# TIA.net
KiCad netlist of a schematic drawn in EAGLE
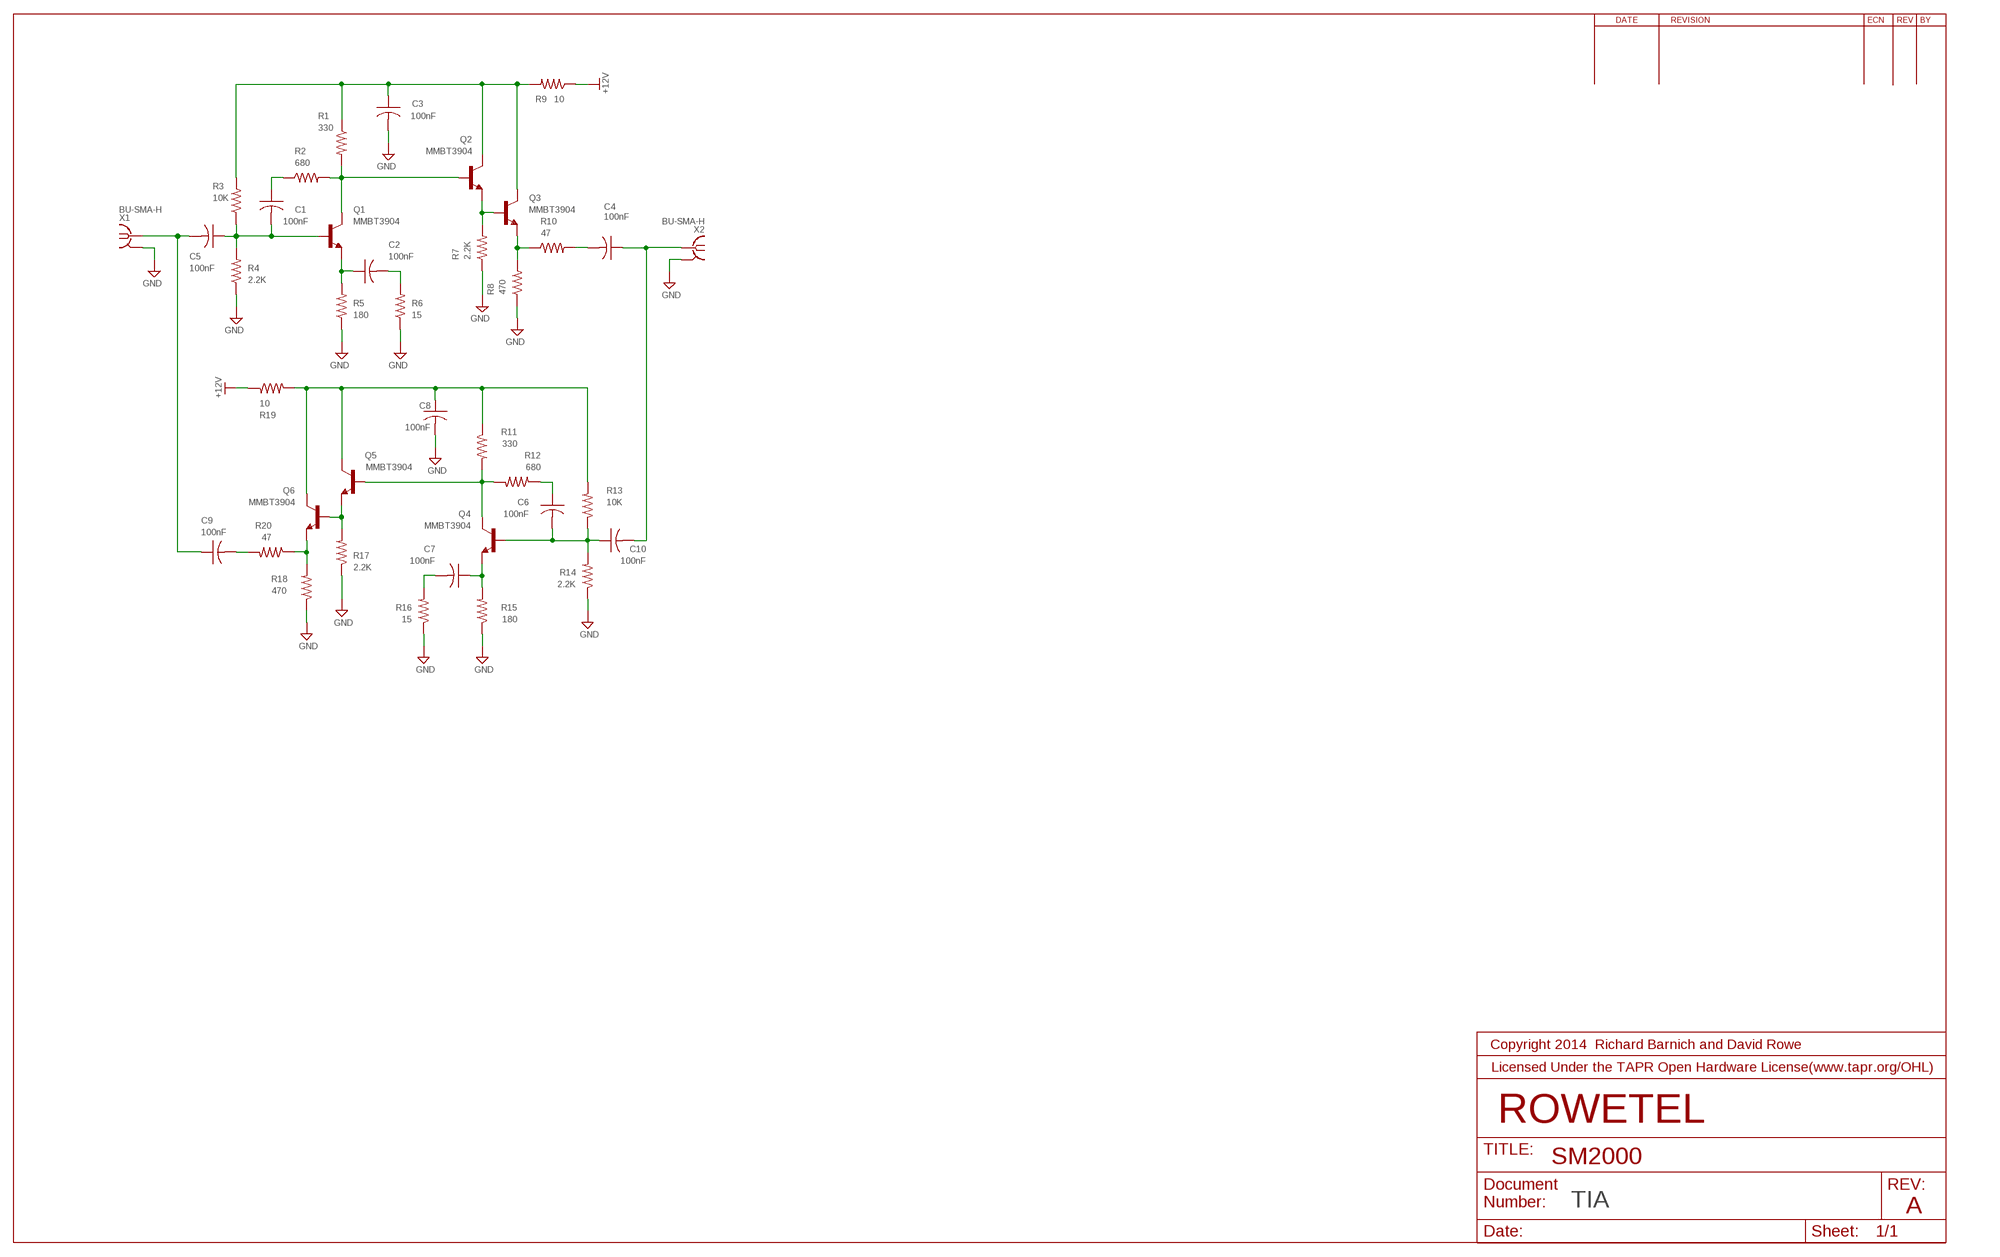
[diagram p0: schematic, sheet 1]

(export (version "E")
  (design (tool "Eeschema 10.0.6"))
  (components
    (comp (ref "C1")
      (value "100nF")
      (footprint "eagle-import:C0805")
      (libsource (lib "eagle-import") (part "CAP-0805"))
    )
    (comp (ref "C2")
      (value "100nF")
      (footprint "eagle-import:C0805")
      (libsource (lib "eagle-import") (part "CAP-0805"))
    )
    (comp (ref "C3")
      (value "100nF")
      (footprint "eagle-import:C0805")
      (libsource (lib "eagle-import") (part "CAP-0805"))
    )
    (comp (ref "C4")
      (value "100nF")
      (footprint "eagle-import:C0805")
      (libsource (lib "eagle-import") (part "CAP-0805"))
    )
    (comp (ref "C5")
      (value "100nF")
      (footprint "eagle-import:C0805")
      (libsource (lib "eagle-import") (part "CAP-0805"))
    )
    (comp (ref "C6")
      (value "100nF")
      (footprint "eagle-import:C0805")
      (libsource (lib "eagle-import") (part "CAP-0805"))
    )
    (comp (ref "C7")
      (value "100nF")
      (footprint "eagle-import:C0805")
      (libsource (lib "eagle-import") (part "CAP-0805"))
    )
    (comp (ref "C8")
      (value "100nF")
      (footprint "eagle-import:C0805")
      (libsource (lib "eagle-import") (part "CAP-0805"))
    )
    (comp (ref "C9")
      (value "100nF")
      (footprint "eagle-import:C0805")
      (libsource (lib "eagle-import") (part "CAP-0805"))
    )
    (comp (ref "C10")
      (value "100nF")
      (footprint "eagle-import:C0805")
      (libsource (lib "eagle-import") (part "CAP-0805"))
    )
    (comp (ref "Q1")
      (value "MMBT3904")
      (footprint "eagle-import:SOT23")
      (libsource (lib "eagle-import") (part "MMBT3904"))
    )
    (comp (ref "Q2")
      (value "MMBT3904")
      (footprint "eagle-import:SOT23")
      (libsource (lib "eagle-import") (part "MMBT3904"))
    )
    (comp (ref "Q3")
      (value "MMBT3904")
      (footprint "eagle-import:SOT23")
      (libsource (lib "eagle-import") (part "MMBT3904"))
    )
    (comp (ref "Q4")
      (value "MMBT3904")
      (footprint "eagle-import:SOT23")
      (libsource (lib "eagle-import") (part "MMBT3904"))
    )
    (comp (ref "Q5")
      (value "MMBT3904")
      (footprint "eagle-import:SOT23")
      (libsource (lib "eagle-import") (part "MMBT3904"))
    )
    (comp (ref "Q6")
      (value "MMBT3904")
      (footprint "eagle-import:SOT23")
      (libsource (lib "eagle-import") (part "MMBT3904"))
    )
    (comp (ref "R1")
      (value "330")
      (footprint "eagle-import:RR0805")
      (libsource (lib "eagle-import") (part "RES0805"))
    )
    (comp (ref "R2")
      (value "680")
      (footprint "eagle-import:RR0805")
      (libsource (lib "eagle-import") (part "RES0805"))
    )
    (comp (ref "R3")
      (value "10K")
      (footprint "eagle-import:RR0805")
      (libsource (lib "eagle-import") (part "RES0805"))
    )
    (comp (ref "R4")
      (value "2.2K")
      (footprint "eagle-import:RR0805")
      (libsource (lib "eagle-import") (part "RES0805"))
    )
    (comp (ref "R5")
      (value "180")
      (footprint "eagle-import:RR0805")
      (libsource (lib "eagle-import") (part "RES0805"))
    )
    (comp (ref "R6")
      (value "15")
      (footprint "eagle-import:RR0805")
      (libsource (lib "eagle-import") (part "RES0805"))
    )
    (comp (ref "R7")
      (value "2.2K")
      (footprint "eagle-import:RR0805")
      (libsource (lib "eagle-import") (part "RES0805"))
    )
    (comp (ref "R8")
      (value "470")
      (footprint "eagle-import:RR0805")
      (libsource (lib "eagle-import") (part "RES0805"))
    )
    (comp (ref "R9")
      (value "10")
      (footprint "eagle-import:RR0805")
      (libsource (lib "eagle-import") (part "RES0805"))
    )
    (comp (ref "R10")
      (value "47")
      (footprint "eagle-import:RR0805")
      (libsource (lib "eagle-import") (part "RES0805"))
    )
    (comp (ref "R11")
      (value "330")
      (footprint "eagle-import:RR0805")
      (libsource (lib "eagle-import") (part "RES0805"))
    )
    (comp (ref "R12")
      (value "680")
      (footprint "eagle-import:RR0805")
      (libsource (lib "eagle-import") (part "RES0805"))
    )
    (comp (ref "R13")
      (value "10K")
      (footprint "eagle-import:RR0805")
      (libsource (lib "eagle-import") (part "RES0805"))
    )
    (comp (ref "R14")
      (value "2.2K")
      (footprint "eagle-import:RR0805")
      (libsource (lib "eagle-import") (part "RES0805"))
    )
    (comp (ref "R15")
      (value "180")
      (footprint "eagle-import:RR0805")
      (libsource (lib "eagle-import") (part "RES0805"))
    )
    (comp (ref "R16")
      (value "15")
      (footprint "eagle-import:RR0805")
      (libsource (lib "eagle-import") (part "RES0805"))
    )
    (comp (ref "R17")
      (value "2.2K")
      (footprint "eagle-import:RR0805")
      (libsource (lib "eagle-import") (part "RES0805"))
    )
    (comp (ref "R18")
      (value "470")
      (footprint "eagle-import:RR0805")
      (libsource (lib "eagle-import") (part "RES0805"))
    )
    (comp (ref "R19")
      (value "10")
      (footprint "eagle-import:RR0805")
      (libsource (lib "eagle-import") (part "RES0805"))
    )
    (comp (ref "R20")
      (value "47")
      (footprint "eagle-import:RR0805")
      (libsource (lib "eagle-import") (part "RES0805"))
    )
    (comp (ref "X1")
      (value "BU-SMA-H")
      (footprint "eagle-import:BU-SMA-H")
      (libsource (lib "eagle-import") (part "BU-SMA-H"))
    )
    (comp (ref "X2")
      (value "BU-SMA-H")
      (footprint "eagle-import:BU-SMA-H")
      (libsource (lib "eagle-import") (part "BU-SMA-H"))
    )
  )
  (nets
    (net (code "1") (name "+12V") (class "Default")
      (node (ref "R19") (pin "1") (pinfunction "1_1") (pintype "passive"))
      (node (ref "R9") (pin "1") (pinfunction "1_1") (pintype "passive"))
    )
    (net (code "2") (name "GND") (class "Default")
      (node (ref "C3") (pin "2") (pinfunction "2_2") (pintype "passive"))
      (node (ref "C8") (pin "2") (pinfunction "2_2") (pintype "passive"))
      (node (ref "R14") (pin "1") (pinfunction "1_1") (pintype "passive"))
      (node (ref "R15") (pin "1") (pinfunction "1_1") (pintype "passive"))
      (node (ref "R16") (pin "1") (pinfunction "1_1") (pintype "passive"))
      (node (ref "R17") (pin "1") (pinfunction "1_1") (pintype "passive"))
      (node (ref "R18") (pin "1") (pinfunction "1_1") (pintype "passive"))
      (node (ref "R4") (pin "1") (pinfunction "1_1") (pintype "passive"))
      (node (ref "R5") (pin "1") (pinfunction "1_1") (pintype "passive"))
      (node (ref "R6") (pin "1") (pinfunction "1_1") (pintype "passive"))
      (node (ref "R7") (pin "1") (pinfunction "1_1") (pintype "passive"))
      (node (ref "R8") (pin "1") (pinfunction "1_1") (pintype "passive"))
      (node (ref "X1") (pin "2") (pinfunction "2_2") (pintype "passive"))
      (node (ref "X1") (pin "3") (pinfunction "2_3") (pintype "passive"))
      (node (ref "X1") (pin "4") (pinfunction "2_4") (pintype "passive"))
      (node (ref "X1") (pin "5") (pinfunction "2_5") (pintype "passive"))
      (node (ref "X2") (pin "2") (pinfunction "2_2") (pintype "passive"))
      (node (ref "X2") (pin "3") (pinfunction "2_3") (pintype "passive"))
      (node (ref "X2") (pin "4") (pinfunction "2_4") (pintype "passive"))
      (node (ref "X2") (pin "5") (pinfunction "2_5") (pintype "passive"))
    )
    (net (code "3") (name "Net-(C1-Pad1)") (class "Default")
      (node (ref "C1") (pin "1") (pinfunction "1_1") (pintype "passive"))
      (node (ref "R2") (pin "1") (pinfunction "1_1") (pintype "passive"))
    )
    (net (code "4") (name "Net-(C2-Pad2)") (class "Default")
      (node (ref "C2") (pin "2") (pinfunction "2_2") (pintype "passive"))
      (node (ref "R6") (pin "2") (pinfunction "2_2") (pintype "passive"))
    )
    (net (code "5") (name "Net-(C4-Pad2)") (class "Default")
      (node (ref "C4") (pin "2") (pinfunction "2_2") (pintype "passive"))
      (node (ref "R10") (pin "2") (pinfunction "2_2") (pintype "passive"))
    )
    (net (code "6") (name "Net-(C5-Pad2)") (class "Default")
      (node (ref "C5") (pin "2") (pinfunction "2_2") (pintype "passive"))
      (node (ref "C9") (pin "1") (pinfunction "1_1") (pintype "passive"))
      (node (ref "X1") (pin "1") (pinfunction "1_1") (pintype "passive"))
    )
    (net (code "7") (name "Net-(C6-Pad1)") (class "Default")
      (node (ref "C6") (pin "1") (pinfunction "1_1") (pintype "passive"))
      (node (ref "R12") (pin "1") (pinfunction "1_1") (pintype "passive"))
    )
    (net (code "8") (name "Net-(C7-Pad2)") (class "Default")
      (node (ref "C7") (pin "2") (pinfunction "2_2") (pintype "passive"))
      (node (ref "R16") (pin "2") (pinfunction "2_2") (pintype "passive"))
    )
    (net (code "9") (name "Net-(C9-Pad2)") (class "Default")
      (node (ref "C9") (pin "2") (pinfunction "2_2") (pintype "passive"))
      (node (ref "R20") (pin "2") (pinfunction "2_2") (pintype "passive"))
    )
    (net (code "10") (name "Net-(C10-Pad2)") (class "Default")
      (node (ref "C10") (pin "2") (pinfunction "2_2") (pintype "passive"))
      (node (ref "C4") (pin "1") (pinfunction "1_1") (pintype "passive"))
      (node (ref "X2") (pin "1") (pinfunction "1_1") (pintype "passive"))
    )
    (net (code "11") (name "Net-(Q1-B)") (class "Default")
      (node (ref "C1") (pin "2") (pinfunction "2_2") (pintype "passive"))
      (node (ref "C5") (pin "1") (pinfunction "1_1") (pintype "passive"))
      (node (ref "Q1") (pin "1") (pinfunction "B_1") (pintype "passive"))
      (node (ref "R3") (pin "1") (pinfunction "1_1") (pintype "passive"))
      (node (ref "R4") (pin "2") (pinfunction "2_2") (pintype "passive"))
    )
    (net (code "12") (name "Net-(Q1-C)") (class "Default")
      (node (ref "Q1") (pin "3") (pinfunction "C_3") (pintype "passive"))
      (node (ref "Q2") (pin "1") (pinfunction "B_1") (pintype "passive"))
      (node (ref "R1") (pin "2") (pinfunction "2_2") (pintype "passive"))
      (node (ref "R2") (pin "2") (pinfunction "2_2") (pintype "passive"))
    )
    (net (code "13") (name "Net-(Q1-E)") (class "Default")
      (node (ref "C2") (pin "1") (pinfunction "1_1") (pintype "passive"))
      (node (ref "Q1") (pin "2") (pinfunction "E_2") (pintype "passive"))
      (node (ref "R5") (pin "2") (pinfunction "2_2") (pintype "passive"))
    )
    (net (code "14") (name "Net-(Q2-C)") (class "Default")
      (node (ref "C3") (pin "1") (pinfunction "1_1") (pintype "passive"))
      (node (ref "Q2") (pin "3") (pinfunction "C_3") (pintype "passive"))
      (node (ref "Q3") (pin "3") (pinfunction "C_3") (pintype "passive"))
      (node (ref "R1") (pin "1") (pinfunction "1_1") (pintype "passive"))
      (node (ref "R3") (pin "2") (pinfunction "2_2") (pintype "passive"))
      (node (ref "R9") (pin "2") (pinfunction "2_2") (pintype "passive"))
    )
    (net (code "15") (name "Net-(Q2-E)") (class "Default")
      (node (ref "Q2") (pin "2") (pinfunction "E_2") (pintype "passive"))
      (node (ref "Q3") (pin "1") (pinfunction "B_1") (pintype "passive"))
      (node (ref "R7") (pin "2") (pinfunction "2_2") (pintype "passive"))
    )
    (net (code "16") (name "Net-(Q3-E)") (class "Default")
      (node (ref "Q3") (pin "2") (pinfunction "E_2") (pintype "passive"))
      (node (ref "R10") (pin "1") (pinfunction "1_1") (pintype "passive"))
      (node (ref "R8") (pin "2") (pinfunction "2_2") (pintype "passive"))
    )
    (net (code "17") (name "Net-(Q4-B)") (class "Default")
      (node (ref "C10") (pin "1") (pinfunction "1_1") (pintype "passive"))
      (node (ref "C6") (pin "2") (pinfunction "2_2") (pintype "passive"))
      (node (ref "Q4") (pin "1") (pinfunction "B_1") (pintype "passive"))
      (node (ref "R13") (pin "1") (pinfunction "1_1") (pintype "passive"))
      (node (ref "R14") (pin "2") (pinfunction "2_2") (pintype "passive"))
    )
    (net (code "18") (name "Net-(Q4-C)") (class "Default")
      (node (ref "Q4") (pin "3") (pinfunction "C_3") (pintype "passive"))
      (node (ref "Q5") (pin "1") (pinfunction "B_1") (pintype "passive"))
      (node (ref "R11") (pin "2") (pinfunction "2_2") (pintype "passive"))
      (node (ref "R12") (pin "2") (pinfunction "2_2") (pintype "passive"))
    )
    (net (code "19") (name "Net-(Q4-E)") (class "Default")
      (node (ref "C7") (pin "1") (pinfunction "1_1") (pintype "passive"))
      (node (ref "Q4") (pin "2") (pinfunction "E_2") (pintype "passive"))
      (node (ref "R15") (pin "2") (pinfunction "2_2") (pintype "passive"))
    )
    (net (code "20") (name "Net-(Q5-C)") (class "Default")
      (node (ref "C8") (pin "1") (pinfunction "1_1") (pintype "passive"))
      (node (ref "Q5") (pin "3") (pinfunction "C_3") (pintype "passive"))
      (node (ref "Q6") (pin "3") (pinfunction "C_3") (pintype "passive"))
      (node (ref "R11") (pin "1") (pinfunction "1_1") (pintype "passive"))
      (node (ref "R13") (pin "2") (pinfunction "2_2") (pintype "passive"))
      (node (ref "R19") (pin "2") (pinfunction "2_2") (pintype "passive"))
    )
    (net (code "21") (name "Net-(Q5-E)") (class "Default")
      (node (ref "Q5") (pin "2") (pinfunction "E_2") (pintype "passive"))
      (node (ref "Q6") (pin "1") (pinfunction "B_1") (pintype "passive"))
      (node (ref "R17") (pin "2") (pinfunction "2_2") (pintype "passive"))
    )
    (net (code "22") (name "Net-(Q6-E)") (class "Default")
      (node (ref "Q6") (pin "2") (pinfunction "E_2") (pintype "passive"))
      (node (ref "R18") (pin "2") (pinfunction "2_2") (pintype "passive"))
      (node (ref "R20") (pin "1") (pinfunction "1_1") (pintype "passive"))
    )
  )
)
